# trig3_board_de0-nano_-_LTC6957.net
KiCad netlist of a schematic drawn in EAGLE
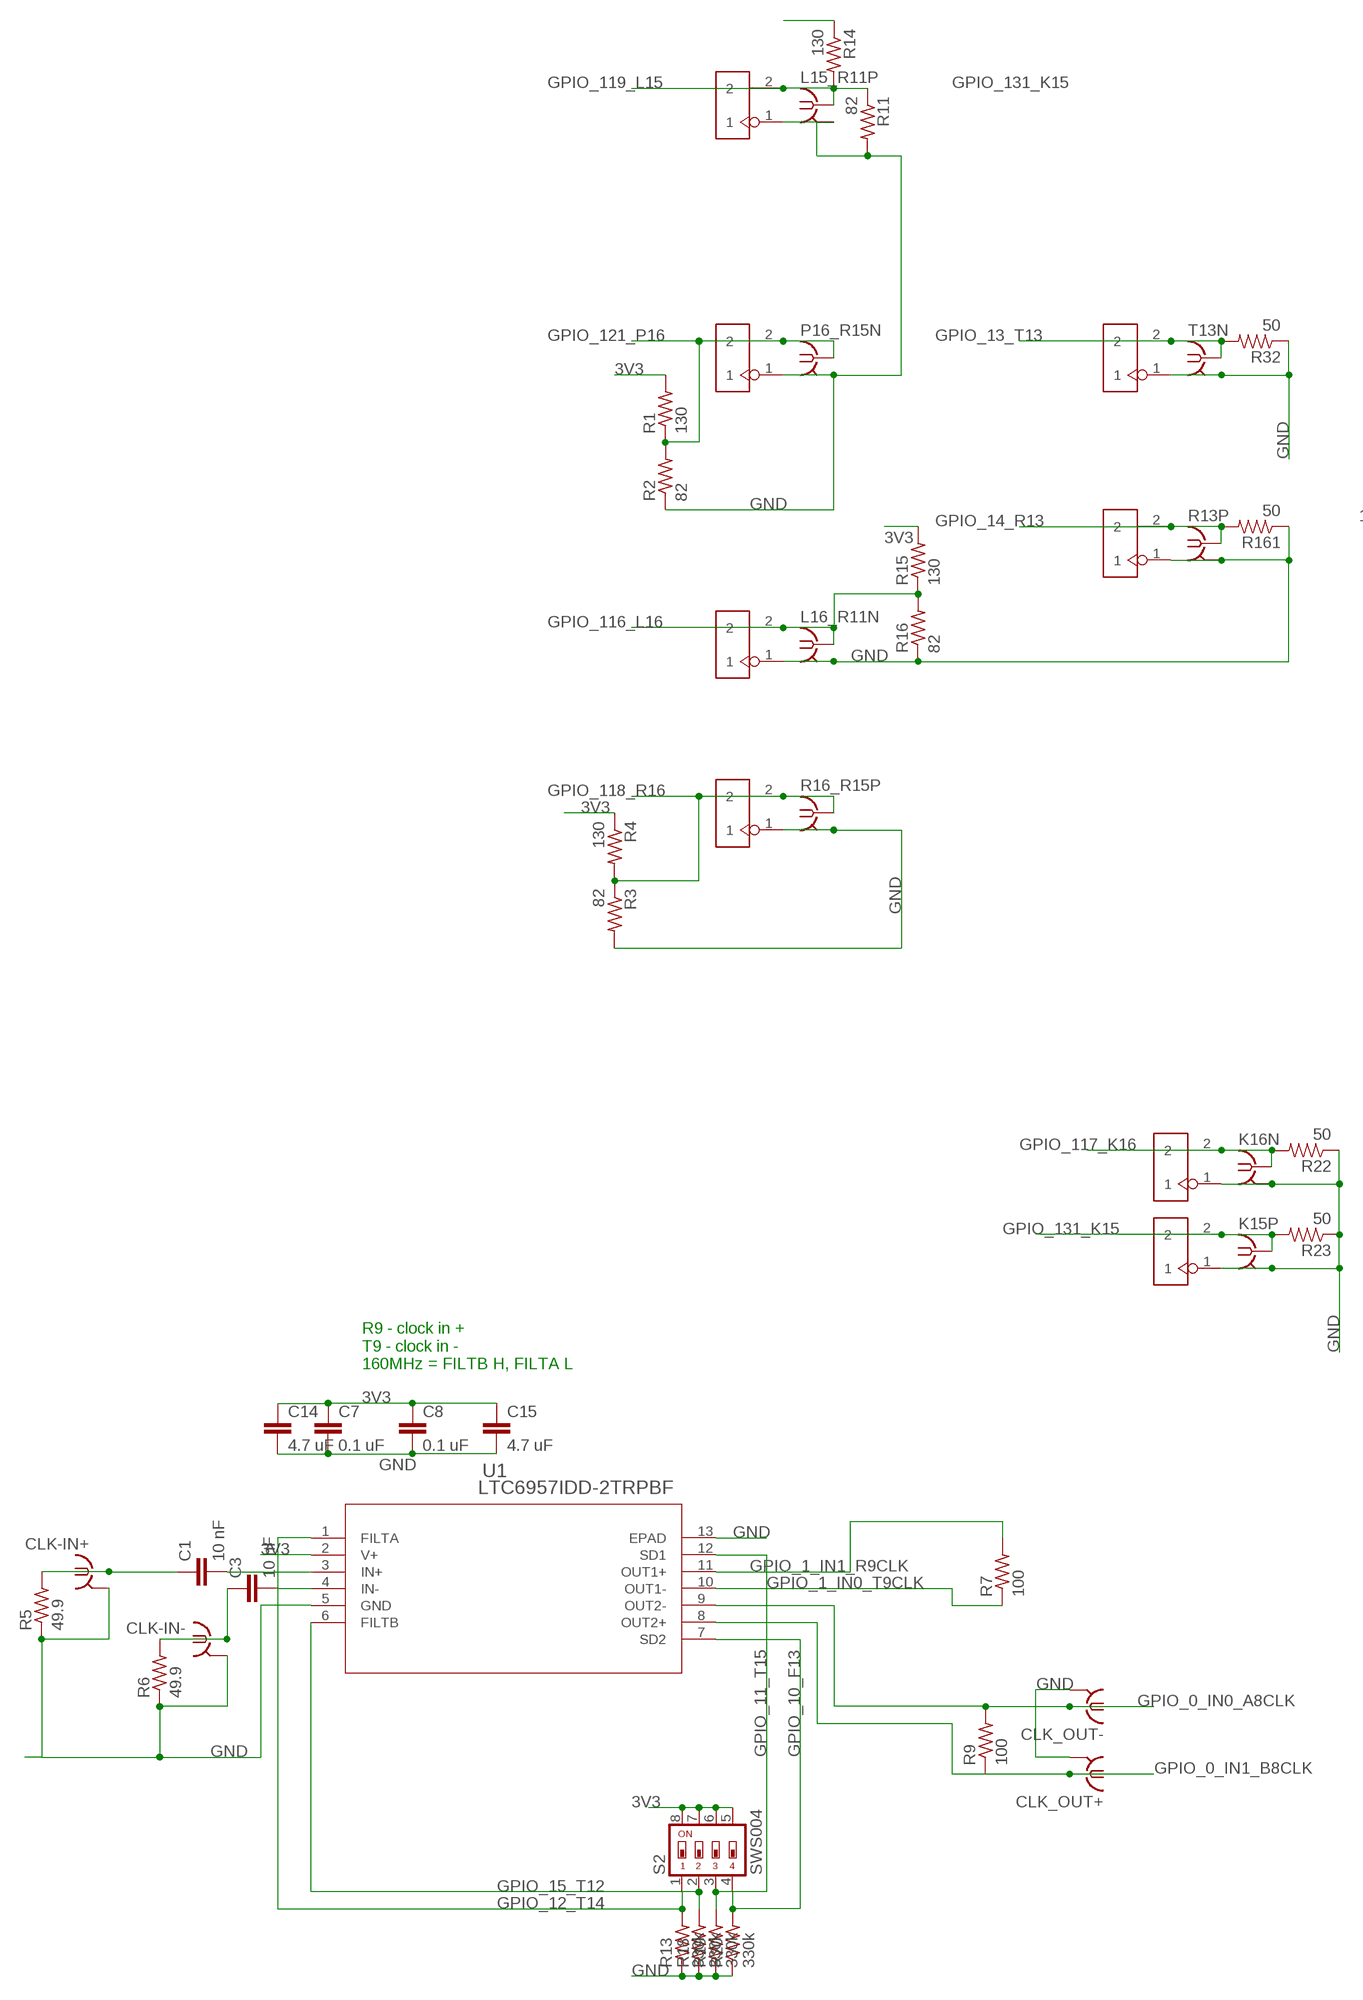
[diagram p0: schematic, sheet 1, part 1 of 2]
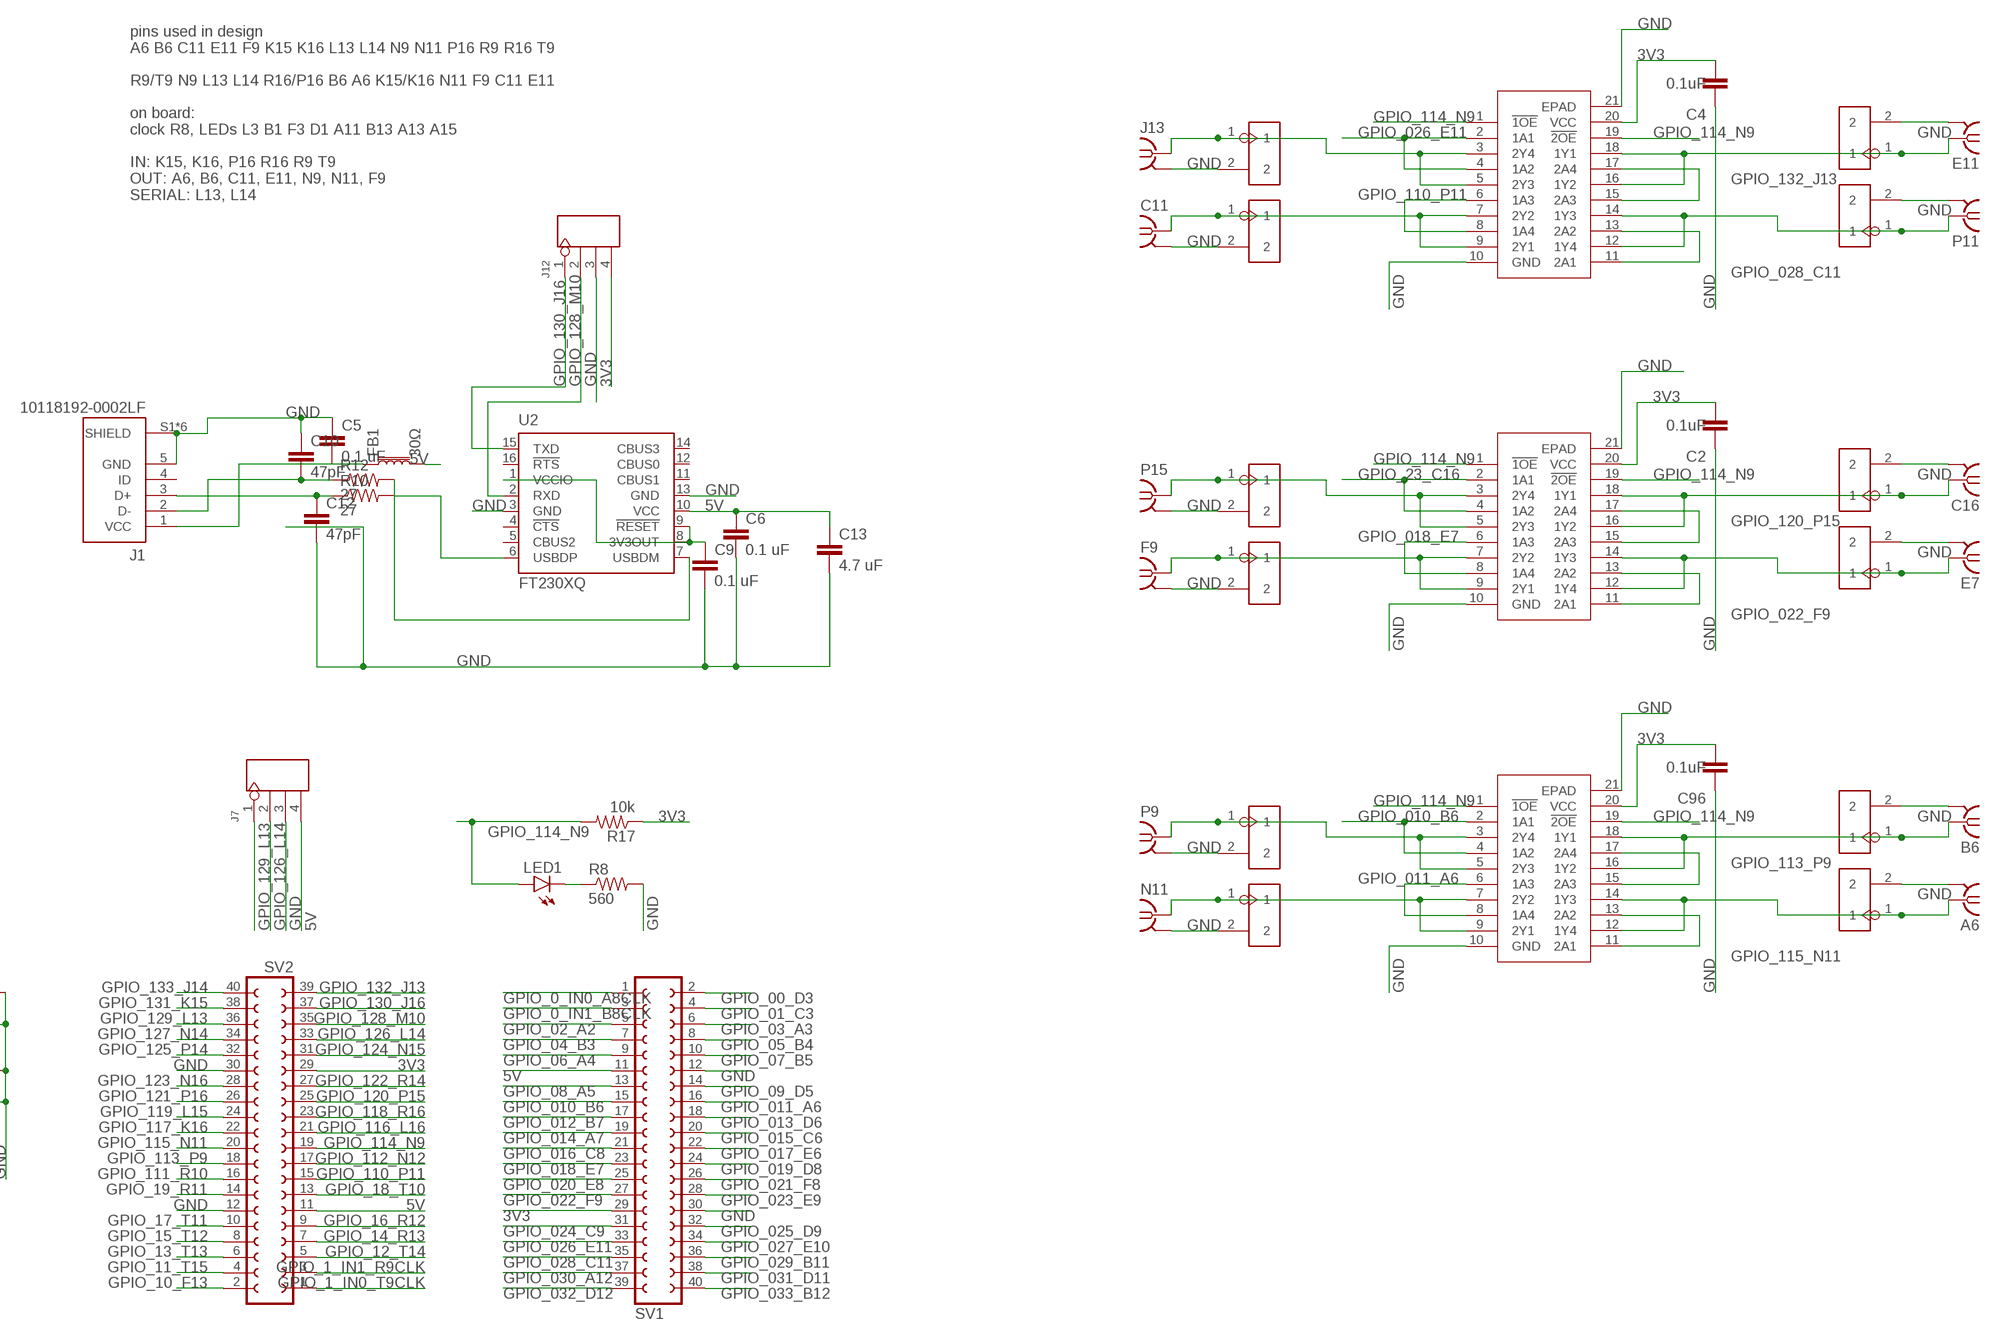
[diagram p1: schematic, sheet 1, part 2 of 2]

(export (version "E")
  (design (tool "Eeschema 10.0.6"))
  (components
    (comp (ref "A6")
      (value "BU-SMB-V")
      (footprint "eagle-import:BU-SMB-V")
      (fields (field (name "LCSC_PART#") "C496549"))
      (libsource (lib "eagle-import") (part "BU-SMB-V"))
    )
    (comp (ref "B6")
      (value "BU-SMB-V")
      (footprint "eagle-import:BU-SMB-V")
      (fields (field (name "LCSC_PART#") "C496549"))
      (libsource (lib "eagle-import") (part "BU-SMB-V"))
    )
    (comp (ref "C1")
      (value "10 nF")
      (footprint "eagle-import:C0603")
      (fields (field (name "LCSC_PART#") "C57112"))
      (libsource (lib "eagle-import") (part "C-EUC0603"))
    )
    (comp (ref "C2")
      (value "0.1uF")
      (footprint "eagle-import:C0603")
      (fields (field (name "LCSC_PART#") "C14663"))
      (libsource (lib "eagle-import") (part "C-EUC0603"))
    )
    (comp (ref "C3")
      (value "10 nF")
      (footprint "eagle-import:C0603")
      (fields (field (name "LCSC_PART#") "C57112"))
      (libsource (lib "eagle-import") (part "C-EUC0603"))
    )
    (comp (ref "C4")
      (value "0.1uF")
      (footprint "eagle-import:C0603")
      (fields (field (name "LCSC_PART#") "C14663"))
      (libsource (lib "eagle-import") (part "C-EUC0603"))
    )
    (comp (ref "C5")
      (value "0.1 uF")
      (footprint "eagle-import:C0603")
      (fields (field (name "LCSC_PART#") "C14663"))
      (libsource (lib "eagle-import") (part "C-EUC0603"))
    )
    (comp (ref "C6")
      (value "0.1 uF")
      (footprint "eagle-import:C0603")
      (fields (field (name "LCSC_PART#") "C14663"))
      (libsource (lib "eagle-import") (part "C-EUC0603"))
    )
    (comp (ref "C7")
      (value "0.1 uF")
      (footprint "eagle-import:C0603")
      (fields (field (name "LCSC_PART#") "C14663"))
      (libsource (lib "eagle-import") (part "C-EUC0603"))
    )
    (comp (ref "C8")
      (value "0.1 uF")
      (footprint "eagle-import:C0603")
      (fields (field (name "LCSC_PART#") "C14663"))
      (libsource (lib "eagle-import") (part "C-EUC0603"))
    )
    (comp (ref "C9")
      (value "0.1 uF")
      (footprint "eagle-import:C0603")
      (fields (field (name "LCSC_PART#") "C14663"))
      (libsource (lib "eagle-import") (part "C-EUC0603"))
    )
    (comp (ref "C10")
      (value "47pF")
      (footprint "eagle-import:C0603")
      (fields (field (name "LCSC_PART#") "C1671"))
      (libsource (lib "eagle-import") (part "C-EUC0603"))
    )
    (comp (ref "C11")
      (value "BU-SMB-V")
      (footprint "eagle-import:BU-SMB-V")
      (fields (field (name "LCSC_PART#") "C496549"))
      (libsource (lib "eagle-import") (part "BU-SMB-V"))
    )
    (comp (ref "C12")
      (value "47pF")
      (footprint "eagle-import:C0603")
      (fields (field (name "LCSC_PART#") "C1671"))
      (libsource (lib "eagle-import") (part "C-EUC0603"))
    )
    (comp (ref "C13")
      (value "4.7 uF")
      (footprint "eagle-import:C0603")
      (fields (field (name "LCSC_PART#") "C19666"))
      (libsource (lib "eagle-import") (part "C-EUC0603"))
    )
    (comp (ref "C14")
      (value "4.7 uF")
      (footprint "eagle-import:C0603")
      (fields (field (name "LCSC_PART#") "C19666"))
      (libsource (lib "eagle-import") (part "C-EUC0603"))
    )
    (comp (ref "C15")
      (value "4.7 uF")
      (footprint "eagle-import:C0603")
      (fields (field (name "LCSC_PART#") "C19666"))
      (libsource (lib "eagle-import") (part "C-EUC0603"))
    )
    (comp (ref "C16")
      (value "BU-SMB-V")
      (footprint "eagle-import:BU-SMB-V")
      (fields (field (name "LCSC_PART#") "C496549"))
      (libsource (lib "eagle-import") (part "BU-SMB-V"))
    )
    (comp (ref "C96")
      (value "0.1uF")
      (footprint "eagle-import:C0603")
      (fields (field (name "LCSC_PART#") "C14663"))
      (libsource (lib "eagle-import") (part "C-EUC0603"))
    )
    (comp (ref "CLK-IN+")
      (value "BU-SMB-V")
      (footprint "eagle-import:BU-SMB-V")
      (fields (field (name "LCSC_PART#") "C496549"))
      (libsource (lib "eagle-import") (part "BU-SMB-V"))
    )
    (comp (ref "CLK-IN-")
      (value "BU-SMB-V")
      (footprint "eagle-import:BU-SMB-V")
      (fields (field (name "LCSC_PART#") "C496549"))
      (libsource (lib "eagle-import") (part "BU-SMB-V"))
    )
    (comp (ref "CLK_OUT+")
      (value "BU-SMB-V")
      (footprint "eagle-import:BU-SMB-V")
      (fields (field (name "LCSC_PART#") "C496549"))
      (libsource (lib "eagle-import") (part "BU-SMB-V"))
    )
    (comp (ref "CLK_OUT-")
      (value "BU-SMB-V")
      (footprint "eagle-import:BU-SMB-V")
      (fields (field (name "LCSC_PART#") "C496549"))
      (libsource (lib "eagle-import") (part "BU-SMB-V"))
    )
    (comp (ref "E7")
      (value "BU-SMB-V")
      (footprint "eagle-import:BU-SMB-V")
      (fields (field (name "LCSC_PART#") "C496549"))
      (libsource (lib "eagle-import") (part "BU-SMB-V"))
    )
    (comp (ref "E11")
      (value "BU-SMB-V")
      (footprint "eagle-import:BU-SMB-V")
      (fields (field (name "LCSC_PART#") "C496549"))
      (libsource (lib "eagle-import") (part "BU-SMB-V"))
    )
    (comp (ref "F9")
      (value "BU-SMB-V")
      (footprint "eagle-import:BU-SMB-V")
      (fields (field (name "LCSC_PART#") "C496549"))
      (libsource (lib "eagle-import") (part "BU-SMB-V"))
    )
    (comp (ref "FB1")
      (value "30Ω")
      (footprint "eagle-import:0603")
      (fields (field (name "LCSC_PART#") "C1002"))
      (libsource (lib "eagle-import") (part "FERRITE_BEAD-0603-30OHM-100MHZ"))
    )
    (comp (ref "J1")
      (value "10118192-0002LF")
      (footprint "eagle-import:AMPHENOL_10118192-0002LF")
      (fields (field (name "MANUFACTURER") "Amphenol") (field (name "LCSC_PART#") "C132564"))
      (libsource (lib "eagle-import") (part "10118192-0002LF"))
    )
    (comp (ref "J7")
      (value "4p-2.54")
      (footprint "eagle-import:H4-2.54")
      (fields (field (name "MPN") "F185-1104A1BSYA1"))
      (libsource (lib "eagle-import") (part "DIP-BLACK-FEMALE-HEADER-VERT(4P-2.54)"))
    )
    (comp (ref "J12")
      (value "4p-2.54")
      (footprint "eagle-import:H4-2.54")
      (fields (field (name "MPN") "F185-1104A1BSYA1"))
      (libsource (lib "eagle-import") (part "DIP-BLACK-FEMALE-HEADER-VERT(4P-2.54)"))
    )
    (comp (ref "J13")
      (value "BU-SMB-V")
      (footprint "eagle-import:BU-SMB-V")
      (fields (field (name "LCSC_PART#") "C496549"))
      (libsource (lib "eagle-import") (part "BU-SMB-V"))
    )
    (comp (ref "J17")
      (value "2p-2.54")
      (footprint "eagle-import:H2-2.54")
      (fields (field (name "MPN") "P125-1102A0BS116A1"))
      (libsource (lib "eagle-import") (part "DIP-BLACK-MALE-HEADER-VERT(2P-2.54)"))
    )
    (comp (ref "J23")
      (value "2p-2.54")
      (footprint "eagle-import:H2-2.54")
      (fields (field (name "MPN") "P125-1102A0BS116A1"))
      (libsource (lib "eagle-import") (part "DIP-BLACK-MALE-HEADER-VERT(2P-2.54)"))
    )
    (comp (ref "J24")
      (value "2p-2.54")
      (footprint "eagle-import:H2-2.54")
      (fields (field (name "MPN") "P125-1102A0BS116A1"))
      (libsource (lib "eagle-import") (part "DIP-BLACK-MALE-HEADER-VERT(2P-2.54)"))
    )
    (comp (ref "J32")
      (value "2p-2.54")
      (footprint "eagle-import:H2-2.54")
      (fields (field (name "MPN") "P125-1102A0BS116A1"))
      (libsource (lib "eagle-import") (part "DIP-BLACK-MALE-HEADER-VERT(2P-2.54)"))
    )
    (comp (ref "J34")
      (value "2p-2.54")
      (footprint "eagle-import:H2-2.54")
      (fields (field (name "MPN") "P125-1102A0BS116A1"))
      (libsource (lib "eagle-import") (part "DIP-BLACK-MALE-HEADER-VERT(2P-2.54)"))
    )
    (comp (ref "J38")
      (value "2p-2.54")
      (footprint "eagle-import:H2-2.54")
      (fields (field (name "MPN") "P125-1102A0BS116A1"))
      (libsource (lib "eagle-import") (part "DIP-BLACK-MALE-HEADER-VERT(2P-2.54)"))
    )
    (comp (ref "J42")
      (value "2p-2.54")
      (footprint "eagle-import:H2-2.54")
      (fields (field (name "MPN") "P125-1102A0BS116A1"))
      (libsource (lib "eagle-import") (part "DIP-BLACK-MALE-HEADER-VERT(2P-2.54)"))
    )
    (comp (ref "J43")
      (value "2p-2.54")
      (footprint "eagle-import:H2-2.54")
      (fields (field (name "MPN") "P125-1102A0BS116A1"))
      (libsource (lib "eagle-import") (part "DIP-BLACK-MALE-HEADER-VERT(2P-2.54)"))
    )
    (comp (ref "K15P")
      (value "BU-SMB-V")
      (footprint "eagle-import:BU-SMB-V")
      (fields (field (name "LCSC_PART#") "C496549"))
      (libsource (lib "eagle-import") (part "BU-SMB-V"))
    )
    (comp (ref "K16N")
      (value "BU-SMB-V")
      (footprint "eagle-import:BU-SMB-V")
      (fields (field (name "LCSC_PART#") "C496549"))
      (libsource (lib "eagle-import") (part "BU-SMB-V"))
    )
    (comp (ref "L15_R11P")
      (value "BU-SMB-V")
      (footprint "eagle-import:BU-SMB-V")
      (fields (field (name "LCSC_PART#") "C496549"))
      (libsource (lib "eagle-import") (part "BU-SMB-V"))
    )
    (comp (ref "L16_R11N")
      (value "BU-SMB-V")
      (footprint "eagle-import:BU-SMB-V")
      (fields (field (name "LCSC_PART#") "C496549"))
      (libsource (lib "eagle-import") (part "BU-SMB-V"))
    )
    (comp (ref "LED1")
      (value "red")
      (footprint "eagle-import:SML0805")
      (fields (field (name "LCSC_PART#") "C84256"))
      (libsource (lib "eagle-import") (part "LEDSML0805"))
    )
    (comp (ref "N11")
      (value "BU-SMB-V")
      (footprint "eagle-import:BU-SMB-V")
      (fields (field (name "LCSC_PART#") "C496549"))
      (libsource (lib "eagle-import") (part "BU-SMB-V"))
    )
    (comp (ref "OJ41")
      (value "2p-2.54")
      (footprint "eagle-import:H2-2.54")
      (fields (field (name "MPN") "P125-1102A0BS116A1"))
      (libsource (lib "eagle-import") (part "DIP-BLACK-MALE-HEADER-VERT(2P-2.54)"))
    )
    (comp (ref "OJ42")
      (value "2p-2.54")
      (footprint "eagle-import:H2-2.54")
      (fields (field (name "MPN") "P125-1102A0BS116A1"))
      (libsource (lib "eagle-import") (part "DIP-BLACK-MALE-HEADER-VERT(2P-2.54)"))
    )
    (comp (ref "OJ43")
      (value "2p-2.54")
      (footprint "eagle-import:H2-2.54")
      (fields (field (name "MPN") "P125-1102A0BS116A1"))
      (libsource (lib "eagle-import") (part "DIP-BLACK-MALE-HEADER-VERT(2P-2.54)"))
    )
    (comp (ref "OJ44")
      (value "2p-2.54")
      (footprint "eagle-import:H2-2.54")
      (fields (field (name "MPN") "P125-1102A0BS116A1"))
      (libsource (lib "eagle-import") (part "DIP-BLACK-MALE-HEADER-VERT(2P-2.54)"))
    )
    (comp (ref "OJ57")
      (value "2p-2.54")
      (footprint "eagle-import:H2-2.54")
      (fields (field (name "MPN") "P125-1102A0BS116A1"))
      (libsource (lib "eagle-import") (part "DIP-BLACK-MALE-HEADER-VERT(2P-2.54)"))
    )
    (comp (ref "OJ58")
      (value "2p-2.54")
      (footprint "eagle-import:H2-2.54")
      (fields (field (name "MPN") "P125-1102A0BS116A1"))
      (libsource (lib "eagle-import") (part "DIP-BLACK-MALE-HEADER-VERT(2P-2.54)"))
    )
    (comp (ref "OJ59")
      (value "2p-2.54")
      (footprint "eagle-import:H2-2.54")
      (fields (field (name "MPN") "P125-1102A0BS116A1"))
      (libsource (lib "eagle-import") (part "DIP-BLACK-MALE-HEADER-VERT(2P-2.54)"))
    )
    (comp (ref "OJ60")
      (value "2p-2.54")
      (footprint "eagle-import:H2-2.54")
      (fields (field (name "MPN") "P125-1102A0BS116A1"))
      (libsource (lib "eagle-import") (part "DIP-BLACK-MALE-HEADER-VERT(2P-2.54)"))
    )
    (comp (ref "OJ73")
      (value "2p-2.54")
      (footprint "eagle-import:H2-2.54")
      (fields (field (name "MPN") "P125-1102A0BS116A1"))
      (libsource (lib "eagle-import") (part "DIP-BLACK-MALE-HEADER-VERT(2P-2.54)"))
    )
    (comp (ref "OJ74")
      (value "2p-2.54")
      (footprint "eagle-import:H2-2.54")
      (fields (field (name "MPN") "P125-1102A0BS116A1"))
      (libsource (lib "eagle-import") (part "DIP-BLACK-MALE-HEADER-VERT(2P-2.54)"))
    )
    (comp (ref "OJ75")
      (value "2p-2.54")
      (footprint "eagle-import:H2-2.54")
      (fields (field (name "MPN") "P125-1102A0BS116A1"))
      (libsource (lib "eagle-import") (part "DIP-BLACK-MALE-HEADER-VERT(2P-2.54)"))
    )
    (comp (ref "OJ76")
      (value "2p-2.54")
      (footprint "eagle-import:H2-2.54")
      (fields (field (name "MPN") "P125-1102A0BS116A1"))
      (libsource (lib "eagle-import") (part "DIP-BLACK-MALE-HEADER-VERT(2P-2.54)"))
    )
    (comp (ref "P9")
      (value "BU-SMB-V")
      (footprint "eagle-import:BU-SMB-V")
      (fields (field (name "LCSC_PART#") "C496549"))
      (libsource (lib "eagle-import") (part "BU-SMB-V"))
    )
    (comp (ref "P11")
      (value "BU-SMB-V")
      (footprint "eagle-import:BU-SMB-V")
      (fields (field (name "LCSC_PART#") "C496549"))
      (libsource (lib "eagle-import") (part "BU-SMB-V"))
    )
    (comp (ref "P15")
      (value "BU-SMB-V")
      (footprint "eagle-import:BU-SMB-V")
      (fields (field (name "LCSC_PART#") "C496549"))
      (libsource (lib "eagle-import") (part "BU-SMB-V"))
    )
    (comp (ref "P16_R15N")
      (value "BU-SMB-V")
      (footprint "eagle-import:BU-SMB-V")
      (fields (field (name "LCSC_PART#") "C496549"))
      (libsource (lib "eagle-import") (part "BU-SMB-V"))
    )
    (comp (ref "R1")
      (value "130")
      (footprint "eagle-import:R0603")
      (fields (field (name "LCSC_PART#") "C22796"))
      (libsource (lib "eagle-import") (part "R-US_R0603"))
    )
    (comp (ref "R2")
      (value "82")
      (footprint "eagle-import:R0603")
      (fields (field (name "LCSC_PART#") "C23255"))
      (libsource (lib "eagle-import") (part "R-US_R0603"))
    )
    (comp (ref "R3")
      (value "82")
      (footprint "eagle-import:R0603")
      (fields (field (name "LCSC_PART#") "C23255"))
      (libsource (lib "eagle-import") (part "R-US_R0603"))
    )
    (comp (ref "R4")
      (value "130")
      (footprint "eagle-import:R0603")
      (fields (field (name "LCSC_PART#") "C22796"))
      (libsource (lib "eagle-import") (part "R-US_R0603"))
    )
    (comp (ref "R5")
      (value "49.9")
      (footprint "eagle-import:R0603")
      (fields (field (name "LCSC_PART#") "C23185"))
      (libsource (lib "eagle-import") (part "R-US_R0603"))
    )
    (comp (ref "R6")
      (value "49.9")
      (footprint "eagle-import:R0603")
      (fields (field (name "LCSC_PART#") "C23185"))
      (libsource (lib "eagle-import") (part "R-US_R0603"))
    )
    (comp (ref "R7")
      (value "100")
      (footprint "eagle-import:R0603")
      (fields (field (name "LCSC_PART#") "C22775"))
      (libsource (lib "eagle-import") (part "R-US_R0603"))
    )
    (comp (ref "R8")
      (value "560")
      (footprint "eagle-import:R0805")
      (fields (field (name "LCSC_PART#") "C28636"))
      (libsource (lib "eagle-import") (part "resistor_348_R-US_R0805"))
    )
    (comp (ref "R9")
      (value "100")
      (footprint "eagle-import:R0603")
      (fields (field (name "LCSC_PART#") "C22775"))
      (libsource (lib "eagle-import") (part "R-US_R0603"))
    )
    (comp (ref "R10")
      (value "27")
      (footprint "eagle-import:R0603")
      (fields (field (name "LCSC_PART#") "C25190"))
      (libsource (lib "eagle-import") (part "R-US_R0603"))
    )
    (comp (ref "R11")
      (value "82")
      (footprint "eagle-import:R0603")
      (fields (field (name "LCSC_PART#") "C23255"))
      (libsource (lib "eagle-import") (part "R-US_R0603"))
    )
    (comp (ref "R12")
      (value "27")
      (footprint "eagle-import:R0603")
      (fields (field (name "LCSC_PART#") "C25190"))
      (libsource (lib "eagle-import") (part "R-US_R0603"))
    )
    (comp (ref "R13")
      (value "330k")
      (footprint "eagle-import:R0603")
      (fields (field (name "LCSC_PART#") "C23137"))
      (libsource (lib "eagle-import") (part "R-US_R0603"))
    )
    (comp (ref "R13P")
      (value "BU-SMB-V")
      (footprint "eagle-import:BU-SMB-V")
      (fields (field (name "LCSC_PART#") "C496549"))
      (libsource (lib "eagle-import") (part "BU-SMB-V"))
    )
    (comp (ref "R14")
      (value "130")
      (footprint "eagle-import:R0603")
      (fields (field (name "LCSC_PART#") "C22796"))
      (libsource (lib "eagle-import") (part "R-US_R0603"))
    )
    (comp (ref "R15")
      (value "130")
      (footprint "eagle-import:R0603")
      (fields (field (name "LCSC_PART#") "C22796"))
      (libsource (lib "eagle-import") (part "R-US_R0603"))
    )
    (comp (ref "R16")
      (value "82")
      (footprint "eagle-import:R0603")
      (fields (field (name "LCSC_PART#") "C23255"))
      (libsource (lib "eagle-import") (part "R-US_R0603"))
    )
    (comp (ref "R16_R15P")
      (value "BU-SMB-V")
      (footprint "eagle-import:BU-SMB-V")
      (fields (field (name "LCSC_PART#") "C496549"))
      (libsource (lib "eagle-import") (part "BU-SMB-V"))
    )
    (comp (ref "R17")
      (value "10k")
      (footprint "eagle-import:AXIAL-0.3")
      (libsource (lib "eagle-import") (part "RESISTORAXIAL-0.3"))
    )
    (comp (ref "R18")
      (value "330k")
      (footprint "eagle-import:R0603")
      (fields (field (name "LCSC_PART#") "C23137"))
      (libsource (lib "eagle-import") (part "R-US_R0603"))
    )
    (comp (ref "R19")
      (value "330k")
      (footprint "eagle-import:R0603")
      (fields (field (name "LCSC_PART#") "C23137"))
      (libsource (lib "eagle-import") (part "R-US_R0603"))
    )
    (comp (ref "R20")
      (value "330k")
      (footprint "eagle-import:R0603")
      (fields (field (name "LCSC_PART#") "C23137"))
      (libsource (lib "eagle-import") (part "R-US_R0603"))
    )
    (comp (ref "R22")
      (value "50")
      (footprint "eagle-import:AXIAL-0.3")
      (libsource (lib "eagle-import") (part "RESISTORAXIAL-0.3"))
    )
    (comp (ref "R23")
      (value "50")
      (footprint "eagle-import:AXIAL-0.3")
      (libsource (lib "eagle-import") (part "RESISTORAXIAL-0.3"))
    )
    (comp (ref "R32")
      (value "50")
      (footprint "eagle-import:AXIAL-0.3")
      (libsource (lib "eagle-import") (part "RESISTORAXIAL-0.3"))
    )
    (comp (ref "R161")
      (value "50")
      (footprint "eagle-import:AXIAL-0.3")
      (libsource (lib "eagle-import") (part "RESISTORAXIAL-0.3"))
    )
    (comp (ref "S2")
      (value "SWS004")
      (footprint "eagle-import:SMS-004")
      (fields (field (name "LCSC_PART#") "C221954"))
      (libsource (lib "eagle-import") (part "SWS004"))
    )
    (comp (ref "SV1")
      (value "FE20-2")
      (footprint "eagle-import:FE20-2")
      (libsource (lib "eagle-import") (part "FE20-2"))
    )
    (comp (ref "SV2")
      (value "FE20-2")
      (footprint "eagle-import:FE20-2")
      (libsource (lib "eagle-import") (part "FE20-2"))
    )
    (comp (ref "T13N")
      (value "BU-SMB-V")
      (footprint "eagle-import:BU-SMB-V")
      (fields (field (name "LCSC_PART#") "C496549"))
      (libsource (lib "eagle-import") (part "BU-SMB-V"))
    )
    (comp (ref "U1")
      (value "LTC6957IDD-2TRPBF")
      (footprint "eagle-import:DFN-12_DD_LIT")
      (fields
        (field (name "MANUFACTURER_PART_NUMBER") "LTC6957IDD-2#TRPBF")
        (field (name "LCSC_PART#") "C689878")
        (field (name "COPYRIGHT") "Copyright (C) 2023 Ultra Librarian. All rights reserved.")
      )
      (libsource (lib "eagle-import") (part "LTC6957IDD-2TRPBF"))
    )
    (comp (ref "U2")
      (value "FT230XQ")
      (footprint "eagle-import:QFN16")
      (fields (field (name "LCSC_PART#") "C128629"))
      (libsource (lib "eagle-import") (part "FT230XQ"))
    )
    (comp (ref "U3")
      (value "SN74LVTH244ARGYR")
      (footprint "eagle-import:RGY20_3P05X2P05")
      (fields
        (field (name "LCSC_PART#") "C2869480")
        (field (name "COPYRIGHT") "Copyright (C) 2023 Ultra Librarian. All rights reserved.")
      )
      (libsource (lib "eagle-import") (part "SN74LVTH244ARGYR"))
    )
    (comp (ref "U4")
      (value "SN74LVTH244ARGYR")
      (footprint "eagle-import:RGY20_3P05X2P05")
      (fields
        (field (name "LCSC_PART#") "C2869480")
        (field (name "COPYRIGHT") "Copyright (C) 2023 Ultra Librarian. All rights reserved.")
      )
      (libsource (lib "eagle-import") (part "SN74LVTH244ARGYR"))
    )
    (comp (ref "U5")
      (value "SN74LVTH244ARGYR")
      (footprint "eagle-import:RGY20_3P05X2P05")
      (fields
        (field (name "LCSC_PART#") "C2869480")
        (field (name "COPYRIGHT") "Copyright (C) 2023 Ultra Librarian. All rights reserved.")
      )
      (libsource (lib "eagle-import") (part "SN74LVTH244ARGYR"))
    )
  )
  (nets
    (net (code "1") (name "/3V3") (class "Default")
      (node (ref "C14") (pin "1") (pinfunction "1_1") (pintype "passive"))
      (node (ref "C15") (pin "1") (pinfunction "1_1") (pintype "passive"))
      (node (ref "C2") (pin "2") (pinfunction "2_2") (pintype "passive"))
      (node (ref "C4") (pin "2") (pinfunction "2_2") (pintype "passive"))
      (node (ref "C7") (pin "1") (pinfunction "1_1") (pintype "passive"))
      (node (ref "C8") (pin "1") (pinfunction "1_1") (pintype "passive"))
      (node (ref "C96") (pin "2") (pinfunction "2_2") (pintype "passive"))
      (node (ref "J12") (pin "4") (pinfunction "P$4_4") (pintype "bidirectional"))
      (node (ref "R1") (pin "2") (pinfunction "2_2") (pintype "passive"))
      (node (ref "R14") (pin "1") (pinfunction "1_1") (pintype "passive"))
      (node (ref "R15") (pin "2") (pinfunction "2_2") (pintype "passive"))
      (node (ref "R17") (pin "P$1") (pinfunction "1_P$1") (pintype "passive"))
      (node (ref "R4") (pin "1") (pinfunction "1_1") (pintype "passive"))
      (node (ref "S2") (pin "5") (pinfunction "5_5") (pintype "passive"))
      (node (ref "S2") (pin "6") (pinfunction "6_6") (pintype "passive"))
      (node (ref "S2") (pin "7") (pinfunction "7_7") (pintype "passive"))
      (node (ref "S2") (pin "8") (pinfunction "8_8") (pintype "passive"))
      (node (ref "SV1") (pin "29") (pinfunction "29_29") (pintype "passive"))
      (node (ref "SV2") (pin "29") (pinfunction "29_29") (pintype "passive"))
      (node (ref "U1") (pin "2") (pinfunction "V+_2") (pintype "power_in"))
      (node (ref "U3") (pin "20") (pinfunction "VCC_20") (pintype "power_in"))
      (node (ref "U4") (pin "20") (pinfunction "VCC_20") (pintype "power_in"))
      (node (ref "U5") (pin "20") (pinfunction "VCC_20") (pintype "power_in"))
    )
    (net (code "2") (name "/5V") (class "Default")
      (node (ref "C13") (pin "1") (pinfunction "1_1") (pintype "passive"))
      (node (ref "C6") (pin "1") (pinfunction "1_1") (pintype "passive"))
      (node (ref "FB1") (pin "2") (pinfunction "2_2") (pintype "passive"))
      (node (ref "J7") (pin "4") (pinfunction "P$4_4") (pintype "bidirectional"))
      (node (ref "SV1") (pin "11") (pinfunction "11_11") (pintype "passive"))
      (node (ref "SV2") (pin "11") (pinfunction "11_11") (pintype "passive"))
      (node (ref "U2") (pin "10") (pinfunction "VCC_10") (pintype "power_in"))
    )
    (net (code "3") (name "/GND") (class "Default")
      (node (ref "A6") (pin "2") (pinfunction "2_2") (pintype "passive"))
      (node (ref "A6") (pin "3") (pinfunction "2_3") (pintype "passive"))
      (node (ref "A6") (pin "4") (pinfunction "2_4") (pintype "passive"))
      (node (ref "A6") (pin "5") (pinfunction "2_5") (pintype "passive"))
      (node (ref "B6") (pin "2") (pinfunction "2_2") (pintype "passive"))
      (node (ref "B6") (pin "3") (pinfunction "2_3") (pintype "passive"))
      (node (ref "B6") (pin "4") (pinfunction "2_4") (pintype "passive"))
      (node (ref "B6") (pin "5") (pinfunction "2_5") (pintype "passive"))
      (node (ref "C10") (pin "1") (pinfunction "1_1") (pintype "passive"))
      (node (ref "C11") (pin "2") (pinfunction "2_2") (pintype "passive"))
      (node (ref "C11") (pin "3") (pinfunction "2_3") (pintype "passive"))
      (node (ref "C11") (pin "4") (pinfunction "2_4") (pintype "passive"))
      (node (ref "C11") (pin "5") (pinfunction "2_5") (pintype "passive"))
      (node (ref "C12") (pin "2") (pinfunction "2_2") (pintype "passive"))
      (node (ref "C13") (pin "2") (pinfunction "2_2") (pintype "passive"))
      (node (ref "C14") (pin "2") (pinfunction "2_2") (pintype "passive"))
      (node (ref "C15") (pin "2") (pinfunction "2_2") (pintype "passive"))
      (node (ref "C16") (pin "2") (pinfunction "2_2") (pintype "passive"))
      (node (ref "C16") (pin "3") (pinfunction "2_3") (pintype "passive"))
      (node (ref "C16") (pin "4") (pinfunction "2_4") (pintype "passive"))
      (node (ref "C16") (pin "5") (pinfunction "2_5") (pintype "passive"))
      (node (ref "C2") (pin "1") (pinfunction "1_1") (pintype "passive"))
      (node (ref "C4") (pin "1") (pinfunction "1_1") (pintype "passive"))
      (node (ref "C5") (pin "1") (pinfunction "1_1") (pintype "passive"))
      (node (ref "C6") (pin "2") (pinfunction "2_2") (pintype "passive"))
      (node (ref "C7") (pin "2") (pinfunction "2_2") (pintype "passive"))
      (node (ref "C8") (pin "2") (pinfunction "2_2") (pintype "passive"))
      (node (ref "C9") (pin "2") (pinfunction "2_2") (pintype "passive"))
      (node (ref "C96") (pin "1") (pinfunction "1_1") (pintype "passive"))
      (node (ref "CLK-IN+") (pin "2") (pinfunction "2_2") (pintype "passive"))
      (node (ref "CLK-IN+") (pin "3") (pinfunction "2_3") (pintype "passive"))
      (node (ref "CLK-IN+") (pin "4") (pinfunction "2_4") (pintype "passive"))
      (node (ref "CLK-IN+") (pin "5") (pinfunction "2_5") (pintype "passive"))
      (node (ref "CLK-IN-") (pin "2") (pinfunction "2_2") (pintype "passive"))
      (node (ref "CLK-IN-") (pin "3") (pinfunction "2_3") (pintype "passive"))
      (node (ref "CLK-IN-") (pin "4") (pinfunction "2_4") (pintype "passive"))
      (node (ref "CLK-IN-") (pin "5") (pinfunction "2_5") (pintype "passive"))
      (node (ref "CLK_OUT+") (pin "2") (pinfunction "2_2") (pintype "passive"))
      (node (ref "CLK_OUT+") (pin "3") (pinfunction "2_3") (pintype "passive"))
      (node (ref "CLK_OUT+") (pin "4") (pinfunction "2_4") (pintype "passive"))
      (node (ref "CLK_OUT+") (pin "5") (pinfunction "2_5") (pintype "passive"))
      (node (ref "CLK_OUT-") (pin "2") (pinfunction "2_2") (pintype "passive"))
      (node (ref "CLK_OUT-") (pin "3") (pinfunction "2_3") (pintype "passive"))
      (node (ref "CLK_OUT-") (pin "4") (pinfunction "2_4") (pintype "passive"))
      (node (ref "CLK_OUT-") (pin "5") (pinfunction "2_5") (pintype "passive"))
      (node (ref "E11") (pin "2") (pinfunction "2_2") (pintype "passive"))
      (node (ref "E11") (pin "3") (pinfunction "2_3") (pintype "passive"))
      (node (ref "E11") (pin "4") (pinfunction "2_4") (pintype "passive"))
      (node (ref "E11") (pin "5") (pinfunction "2_5") (pintype "passive"))
      (node (ref "E7") (pin "2") (pinfunction "2_2") (pintype "passive"))
      (node (ref "E7") (pin "3") (pinfunction "2_3") (pintype "passive"))
      (node (ref "E7") (pin "4") (pinfunction "2_4") (pintype "passive"))
      (node (ref "E7") (pin "5") (pinfunction "2_5") (pintype "passive"))
      (node (ref "F9") (pin "2") (pinfunction "2_2") (pintype "passive"))
      (node (ref "F9") (pin "3") (pinfunction "2_3") (pintype "passive"))
      (node (ref "F9") (pin "4") (pinfunction "2_4") (pintype "passive"))
      (node (ref "F9") (pin "5") (pinfunction "2_5") (pintype "passive"))
      (node (ref "J1") (pin "5") (pinfunction "GND_5") (pintype "power_in"))
      (node (ref "J1") (pin "S1") (pinfunction "SHIELD_S1") (pintype "passive"))
      (node (ref "J1") (pin "S2") (pinfunction "SHIELD_S2") (pintype "passive"))
      (node (ref "J1") (pin "S3") (pinfunction "SHIELD_S3") (pintype "passive"))
      (node (ref "J1") (pin "S4") (pinfunction "SHIELD_S4") (pintype "passive"))
      (node (ref "J1") (pin "S5") (pinfunction "SHIELD_S5") (pintype "passive"))
      (node (ref "J1") (pin "S6") (pinfunction "SHIELD_S6") (pintype "passive"))
      (node (ref "J12") (pin "3") (pinfunction "P$3_3") (pintype "bidirectional"))
      (node (ref "J13") (pin "2") (pinfunction "2_2") (pintype "passive"))
      (node (ref "J13") (pin "3") (pinfunction "2_3") (pintype "passive"))
      (node (ref "J13") (pin "4") (pinfunction "2_4") (pintype "passive"))
      (node (ref "J13") (pin "5") (pinfunction "2_5") (pintype "passive"))
      (node (ref "J17") (pin "1") (pinfunction "1_1") (pintype "bidirectional"))
      (node (ref "J23") (pin "1") (pinfunction "1_1") (pintype "bidirectional"))
      (node (ref "J24") (pin "1") (pinfunction "1_1") (pintype "bidirectional"))
      (node (ref "J32") (pin "1") (pinfunction "1_1") (pintype "bidirectional"))
      (node (ref "J34") (pin "1") (pinfunction "1_1") (pintype "bidirectional"))
      (node (ref "J38") (pin "1") (pinfunction "1_1") (pintype "bidirectional"))
      (node (ref "J42") (pin "1") (pinfunction "1_1") (pintype "bidirectional"))
      (node (ref "J43") (pin "1") (pinfunction "1_1") (pintype "bidirectional"))
      (node (ref "J7") (pin "3") (pinfunction "P$3_3") (pintype "bidirectional"))
      (node (ref "K15P") (pin "2") (pinfunction "2_2") (pintype "passive"))
      (node (ref "K15P") (pin "3") (pinfunction "2_3") (pintype "passive"))
      (node (ref "K15P") (pin "4") (pinfunction "2_4") (pintype "passive"))
      (node (ref "K15P") (pin "5") (pinfunction "2_5") (pintype "passive"))
      (node (ref "K16N") (pin "2") (pinfunction "2_2") (pintype "passive"))
      (node (ref "K16N") (pin "3") (pinfunction "2_3") (pintype "passive"))
      (node (ref "K16N") (pin "4") (pinfunction "2_4") (pintype "passive"))
      (node (ref "K16N") (pin "5") (pinfunction "2_5") (pintype "passive"))
      (node (ref "L15_R11P") (pin "2") (pinfunction "2_2") (pintype "passive"))
      (node (ref "L15_R11P") (pin "3") (pinfunction "2_3") (pintype "passive"))
      (node (ref "L15_R11P") (pin "4") (pinfunction "2_4") (pintype "passive"))
      (node (ref "L15_R11P") (pin "5") (pinfunction "2_5") (pintype "passive"))
      (node (ref "L16_R11N") (pin "2") (pinfunction "2_2") (pintype "passive"))
      (node (ref "L16_R11N") (pin "3") (pinfunction "2_3") (pintype "passive"))
      (node (ref "L16_R11N") (pin "4") (pinfunction "2_4") (pintype "passive"))
      (node (ref "L16_R11N") (pin "5") (pinfunction "2_5") (pintype "passive"))
      (node (ref "N11") (pin "2") (pinfunction "2_2") (pintype "passive"))
      (node (ref "N11") (pin "3") (pinfunction "2_3") (pintype "passive"))
      (node (ref "N11") (pin "4") (pinfunction "2_4") (pintype "passive"))
      (node (ref "N11") (pin "5") (pinfunction "2_5") (pintype "passive"))
      (node (ref "OJ41") (pin "2") (pinfunction "2_2") (pintype "bidirectional"))
      (node (ref "OJ42") (pin "2") (pinfunction "2_2") (pintype "bidirectional"))
      (node (ref "OJ43") (pin "2") (pinfunction "2_2") (pintype "bidirectional"))
      (node (ref "OJ44") (pin "2") (pinfunction "2_2") (pintype "bidirectional"))
      (node (ref "OJ57") (pin "2") (pinfunction "2_2") (pintype "bidirectional"))
      (node (ref "OJ58") (pin "2") (pinfunction "2_2") (pintype "bidirectional"))
      (node (ref "OJ59") (pin "2") (pinfunction "2_2") (pintype "bidirectional"))
      (node (ref "OJ60") (pin "2") (pinfunction "2_2") (pintype "bidirectional"))
      (node (ref "OJ73") (pin "2") (pinfunction "2_2") (pintype "bidirectional"))
      (node (ref "OJ74") (pin "2") (pinfunction "2_2") (pintype "bidirectional"))
      (node (ref "OJ75") (pin "2") (pinfunction "2_2") (pintype "bidirectional"))
      (node (ref "OJ76") (pin "2") (pinfunction "2_2") (pintype "bidirectional"))
      (node (ref "P11") (pin "2") (pinfunction "2_2") (pintype "passive"))
      (node (ref "P11") (pin "3") (pinfunction "2_3") (pintype "passive"))
      (node (ref "P11") (pin "4") (pinfunction "2_4") (pintype "passive"))
      (node (ref "P11") (pin "5") (pinfunction "2_5") (pintype "passive"))
      (node (ref "P15") (pin "2") (pinfunction "2_2") (pintype "passive"))
      (node (ref "P15") (pin "3") (pinfunction "2_3") (pintype "passive"))
      (node (ref "P15") (pin "4") (pinfunction "2_4") (pintype "passive"))
      (node (ref "P15") (pin "5") (pinfunction "2_5") (pintype "passive"))
      (node (ref "P16_R15N") (pin "2") (pinfunction "2_2") (pintype "passive"))
      (node (ref "P16_R15N") (pin "3") (pinfunction "2_3") (pintype "passive"))
      (node (ref "P16_R15N") (pin "4") (pinfunction "2_4") (pintype "passive"))
      (node (ref "P16_R15N") (pin "5") (pinfunction "2_5") (pintype "passive"))
      (node (ref "P9") (pin "2") (pinfunction "2_2") (pintype "passive"))
      (node (ref "P9") (pin "3") (pinfunction "2_3") (pintype "passive"))
      (node (ref "P9") (pin "4") (pinfunction "2_4") (pintype "passive"))
      (node (ref "P9") (pin "5") (pinfunction "2_5") (pintype "passive"))
      (node (ref "R11") (pin "2") (pinfunction "2_2") (pintype "passive"))
      (node (ref "R13") (pin "1") (pinfunction "1_1") (pintype "passive"))
      (node (ref "R13P") (pin "2") (pinfunction "2_2") (pintype "passive"))
      (node (ref "R13P") (pin "3") (pinfunction "2_3") (pintype "passive"))
      (node (ref "R13P") (pin "4") (pinfunction "2_4") (pintype "passive"))
      (node (ref "R13P") (pin "5") (pinfunction "2_5") (pintype "passive"))
      (node (ref "R16") (pin "1") (pinfunction "1_1") (pintype "passive"))
      (node (ref "R161") (pin "P$1") (pinfunction "1_P$1") (pintype "passive"))
      (node (ref "R16_R15P") (pin "2") (pinfunction "2_2") (pintype "passive"))
      (node (ref "R16_R15P") (pin "3") (pinfunction "2_3") (pintype "passive"))
      (node (ref "R16_R15P") (pin "4") (pinfunction "2_4") (pintype "passive"))
      (node (ref "R16_R15P") (pin "5") (pinfunction "2_5") (pintype "passive"))
      (node (ref "R18") (pin "1") (pinfunction "1_1") (pintype "passive"))
      (node (ref "R19") (pin "1") (pinfunction "1_1") (pintype "passive"))
      (node (ref "R2") (pin "1") (pinfunction "1_1") (pintype "passive"))
      (node (ref "R20") (pin "1") (pinfunction "1_1") (pintype "passive"))
      (node (ref "R22") (pin "P$1") (pinfunction "1_P$1") (pintype "passive"))
      (node (ref "R23") (pin "P$1") (pinfunction "1_P$1") (pintype "passive"))
      (node (ref "R3") (pin "2") (pinfunction "2_2") (pintype "passive"))
      (node (ref "R32") (pin "P$1") (pinfunction "1_P$1") (pintype "passive"))
      (node (ref "R5") (pin "1") (pinfunction "1_1") (pintype "passive"))
      (node (ref "R6") (pin "1") (pinfunction "1_1") (pintype "passive"))
      (node (ref "R8") (pin "2") (pinfunction "2_2") (pintype "passive"))
      (node (ref "SV1") (pin "12") (pinfunction "12_12") (pintype "passive"))
      (node (ref "SV1") (pin "30") (pinfunction "30_30") (pintype "passive"))
      (node (ref "SV2") (pin "12") (pinfunction "12_12") (pintype "passive"))
      (node (ref "SV2") (pin "30") (pinfunction "30_30") (pintype "passive"))
      (node (ref "T13N") (pin "2") (pinfunction "2_2") (pintype "passive"))
      (node (ref "T13N") (pin "3") (pinfunction "2_3") (pintype "passive"))
      (node (ref "T13N") (pin "4") (pinfunction "2_4") (pintype "passive"))
      (node (ref "T13N") (pin "5") (pinfunction "2_5") (pintype "passive"))
      (node (ref "U1") (pin "13") (pinfunction "EPAD_13") (pintype "passive"))
      (node (ref "U1") (pin "5") (pinfunction "GND_5") (pintype "power_in"))
      (node (ref "U2") (pin "13") (pinfunction "GND_13") (pintype "power_in"))
      (node (ref "U2") (pin "3") (pinfunction "GND_3") (pintype "power_in"))
      (node (ref "U3") (pin "10") (pinfunction "GND_10") (pintype "power_in"))
      (node (ref "U3") (pin "21") (pinfunction "EPAD_21") (pintype "passive"))
      (node (ref "U4") (pin "10") (pinfunction "GND_10") (pintype "power_in"))
      (node (ref "U4") (pin "21") (pinfunction "EPAD_21") (pintype "passive"))
      (node (ref "U5") (pin "10") (pinfunction "GND_10") (pintype "power_in"))
      (node (ref "U5") (pin "21") (pinfunction "EPAD_21") (pintype "passive"))
    )
    (net (code "4") (name "/GPIO_00_D3") (class "Default")
      (node (ref "SV1") (pin "2") (pinfunction "2_2") (pintype "passive"))
    )
    (net (code "5") (name "/GPIO_0_IN0_A8CLK") (class "Default")
      (node (ref "CLK_OUT-") (pin "1") (pinfunction "1_1") (pintype "passive"))
      (node (ref "R9") (pin "2") (pinfunction "2_2") (pintype "passive"))
      (node (ref "SV1") (pin "1") (pinfunction "1_1") (pintype "passive"))
      (node (ref "U1") (pin "9") (pinfunction "OUT2-_9") (pintype "output"))
    )
    (net (code "6") (name "/GPIO_0_IN1_B8CLK") (class "Default")
      (node (ref "CLK_OUT+") (pin "1") (pinfunction "1_1") (pintype "passive"))
      (node (ref "R9") (pin "1") (pinfunction "1_1") (pintype "passive"))
      (node (ref "SV1") (pin "3") (pinfunction "3_3") (pintype "passive"))
      (node (ref "U1") (pin "8") (pinfunction "OUT2+_8") (pintype "output"))
    )
    (net (code "7") (name "/GPIO_01_C3") (class "Default")
      (node (ref "SV1") (pin "4") (pinfunction "4_4") (pintype "passive"))
    )
    (net (code "8") (name "/GPIO_1_IN0_T9CLK") (class "Default")
      (node (ref "R7") (pin "1") (pinfunction "1_1") (pintype "passive"))
      (node (ref "SV2") (pin "1") (pinfunction "1_1") (pintype "passive"))
      (node (ref "U1") (pin "10") (pinfunction "OUT1-_10") (pintype "output"))
    )
    (net (code "9") (name "/GPIO_1_IN1_R9CLK") (class "Default")
      (node (ref "R7") (pin "2") (pinfunction "2_2") (pintype "passive"))
      (node (ref "SV2") (pin "3") (pinfunction "3_3") (pintype "passive"))
      (node (ref "U1") (pin "11") (pinfunction "OUT1+_11") (pintype "power_in"))
    )
    (net (code "10") (name "/GPIO_02_A2") (class "Default")
      (node (ref "SV1") (pin "5") (pinfunction "5_5") (pintype "passive"))
    )
    (net (code "11") (name "/GPIO_03_A3") (class "Default")
      (node (ref "SV1") (pin "6") (pinfunction "6_6") (pintype "passive"))
    )
    (net (code "12") (name "/GPIO_04_B3") (class "Default")
      (node (ref "SV1") (pin "7") (pinfunction "7_7") (pintype "passive"))
    )
    (net (code "13") (name "/GPIO_05_B4") (class "Default")
      (node (ref "SV1") (pin "8") (pinfunction "8_8") (pintype "passive"))
    )
    (net (code "14") (name "/GPIO_06_A4") (class "Default")
      (node (ref "SV1") (pin "9") (pinfunction "9_9") (pintype "passive"))
    )
    (net (code "15") (name "/GPIO_07_B5") (class "Default")
      (node (ref "SV1") (pin "10") (pinfunction "10_10") (pintype "passive"))
    )
    (net (code "16") (name "/GPIO_08_A5") (class "Default")
      (node (ref "SV1") (pin "13") (pinfunction "13_13") (pintype "passive"))
    )
    (net (code "17") (name "/GPIO_09_D5") (class "Default")
      (node (ref "SV1") (pin "14") (pinfunction "14_14") (pintype "passive"))
    )
    (net (code "18") (name "/GPIO_010_B6") (class "Default")
      (node (ref "SV1") (pin "15") (pinfunction "15_15") (pintype "passive"))
      (node (ref "U5") (pin "2") (pinfunction "1A1_2") (pintype "input"))
      (node (ref "U5") (pin "4") (pinfunction "1A2_4") (pintype "input"))
    )
    (net (code "19") (name "/GPIO_10_F13") (class "Default")
      (node (ref "R20") (pin "2") (pinfunction "2_2") (pintype "passive"))
      (node (ref "S2") (pin "4") (pinfunction "4_4") (pintype "passive"))
      (node (ref "SV2") (pin "2") (pinfunction "2_2") (pintype "passive"))
      (node (ref "U1") (pin "7") (pinfunction "SD2_7") (pintype "output"))
    )
    (net (code "20") (name "/GPIO_011_A6") (class "Default")
      (node (ref "SV1") (pin "16") (pinfunction "16_16") (pintype "passive"))
      (node (ref "U5") (pin "6") (pinfunction "1A3_6") (pintype "input"))
      (node (ref "U5") (pin "8") (pinfunction "1A4_8") (pintype "input"))
    )
    (net (code "21") (name "/GPIO_11_T15") (class "Default")
      (node (ref "R19") (pin "2") (pinfunction "2_2") (pintype "passive"))
      (node (ref "S2") (pin "3") (pinfunction "3_3") (pintype "passive"))
      (node (ref "SV2") (pin "4") (pinfunction "4_4") (pintype "passive"))
      (node (ref "U1") (pin "12") (pinfunction "SD1_12") (pintype "output"))
    )
    (net (code "22") (name "/GPIO_012_B7") (class "Default")
      (node (ref "SV1") (pin "17") (pinfunction "17_17") (pintype "passive"))
    )
    (net (code "23") (name "/GPIO_12_T14") (class "Default")
      (node (ref "R13") (pin "2") (pinfunction "2_2") (pintype "passive"))
      (node (ref "S2") (pin "1") (pinfunction "1_1") (pintype "passive"))
      (node (ref "SV2") (pin "5") (pinfunction "5_5") (pintype "passive"))
      (node (ref "U1") (pin "1") (pinfunction "FILTA_1") (pintype "input"))
    )
    (net (code "24") (name "/GPIO_013_D6") (class "Default")
      (node (ref "SV1") (pin "18") (pinfunction "18_18") (pintype "passive"))
    )
    (net (code "25") (name "/GPIO_13_T13") (class "Default")
      (node (ref "J38") (pin "2") (pinfunction "2_2") (pintype "bidirectional"))
      (node (ref "R32") (pin "P$2") (pinfunction "2_P$2") (pintype "passive"))
      (node (ref "SV2") (pin "6") (pinfunction "6_6") (pintype "passive"))
      (node (ref "T13N") (pin "1") (pinfunction "1_1") (pintype "passive"))
    )
    (net (code "26") (name "/GPIO_014_A7") (class "Default")
      (node (ref "SV1") (pin "19") (pinfunction "19_19") (pintype "passive"))
    )
    (net (code "27") (name "/GPIO_14_R13") (class "Default")
      (node (ref "J17") (pin "2") (pinfunction "2_2") (pintype "bidirectional"))
      (node (ref "R13P") (pin "1") (pinfunction "1_1") (pintype "passive"))
      (node (ref "R161") (pin "P$2") (pinfunction "2_P$2") (pintype "passive"))
      (node (ref "SV2") (pin "7") (pinfunction "7_7") (pintype "passive"))
    )
    (net (code "28") (name "/GPIO_015_C6") (class "Default")
      (node (ref "SV1") (pin "20") (pinfunction "20_20") (pintype "passive"))
    )
    (net (code "29") (name "/GPIO_15_T12") (class "Default")
      (node (ref "R18") (pin "2") (pinfunction "2_2") (pintype "passive"))
      (node (ref "S2") (pin "2") (pinfunction "2_2") (pintype "passive"))
      (node (ref "SV2") (pin "8") (pinfunction "8_8") (pintype "passive"))
      (node (ref "U1") (pin "6") (pinfunction "FILTB_6") (pintype "input"))
    )
    (net (code "30") (name "/GPIO_016_C8") (class "Default")
      (node (ref "SV1") (pin "21") (pinfunction "21_21") (pintype "passive"))
    )
    (net (code "31") (name "/GPIO_16_R12") (class "Default")
      (node (ref "SV2") (pin "9") (pinfunction "9_9") (pintype "passive"))
    )
    (net (code "32") (name "/GPIO_017_E6") (class "Default")
      (node (ref "SV1") (pin "22") (pinfunction "22_22") (pintype "passive"))
    )
    (net (code "33") (name "/GPIO_17_T11") (class "Default")
      (node (ref "SV2") (pin "10") (pinfunction "10_10") (pintype "passive"))
    )
    (net (code "34") (name "/GPIO_018_E7") (class "Default")
      (node (ref "SV1") (pin "23") (pinfunction "23_23") (pintype "passive"))
      (node (ref "U4") (pin "6") (pinfunction "1A3_6") (pintype "input"))
      (node (ref "U4") (pin "8") (pinfunction "1A4_8") (pintype "input"))
    )
    (net (code "35") (name "/GPIO_18_T10") (class "Default")
      (node (ref "SV2") (pin "13") (pinfunction "13_13") (pintype "passive"))
    )
    (net (code "36") (name "/GPIO_019_D8") (class "Default")
      (node (ref "SV1") (pin "24") (pinfunction "24_24") (pintype "passive"))
    )
    (net (code "37") (name "/GPIO_19_R11") (class "Default")
      (node (ref "SV2") (pin "14") (pinfunction "14_14") (pintype "passive"))
    )
    (net (code "38") (name "/GPIO_020_E8") (class "Default")
      (node (ref "SV1") (pin "25") (pinfunction "25_25") (pintype "passive"))
    )
    (net (code "39") (name "/GPIO_021_F8") (class "Default")
      (node (ref "SV1") (pin "26") (pinfunction "26_26") (pintype "passive"))
    )
    (net (code "40") (name "/GPIO_022_F9") (class "Default")
      (node (ref "SV1") (pin "27") (pinfunction "27_27") (pintype "passive"))
      (node (ref "U4") (pin "11") (pinfunction "2A1_11") (pintype "input"))
      (node (ref "U4") (pin "13") (pinfunction "2A2_13") (pintype "input"))
    )
    (net (code "41") (name "/GPIO_23_C16") (class "Default")
      (node (ref "U4") (pin "2") (pinfunction "1A1_2") (pintype "input"))
      (node (ref "U4") (pin "4") (pinfunction "1A2_4") (pintype "input"))
    )
    (net (code "42") (name "/GPIO_023_E9") (class "Default")
      (node (ref "SV1") (pin "28") (pinfunction "28_28") (pintype "passive"))
    )
    (net (code "43") (name "/GPIO_024_C9") (class "Default")
      (node (ref "SV1") (pin "31") (pinfunction "31_31") (pintype "passive"))
    )
    (net (code "44") (name "/GPIO_025_D9") (class "Default")
      (node (ref "SV1") (pin "32") (pinfunction "32_32") (pintype "passive"))
    )
    (net (code "45") (name "/GPIO_026_E11") (class "Default")
      (node (ref "SV1") (pin "33") (pinfunction "33_33") (pintype "passive"))
      (node (ref "U3") (pin "2") (pinfunction "1A1_2") (pintype "input"))
      (node (ref "U3") (pin "4") (pinfunction "1A2_4") (pintype "input"))
    )
    (net (code "46") (name "/GPIO_027_E10") (class "Default")
      (node (ref "SV1") (pin "34") (pinfunction "34_34") (pintype "passive"))
    )
    (net (code "47") (name "/GPIO_028_C11") (class "Default")
      (node (ref "SV1") (pin "35") (pinfunction "35_35") (pintype "passive"))
      (node (ref "U3") (pin "11") (pinfunction "2A1_11") (pintype "input"))
      (node (ref "U3") (pin "13") (pinfunction "2A2_13") (pintype "input"))
    )
    (net (code "48") (name "/GPIO_029_B11") (class "Default")
      (node (ref "SV1") (pin "36") (pinfunction "36_36") (pintype "passive"))
    )
    (net (code "49") (name "/GPIO_030_A12") (class "Default")
      (node (ref "SV1") (pin "37") (pinfunction "37_37") (pintype "passive"))
    )
    (net (code "50") (name "/GPIO_031_D11") (class "Default")
      (node (ref "SV1") (pin "38") (pinfunction "38_38") (pintype "passive"))
    )
    (net (code "51") (name "/GPIO_032_D12") (class "Default")
      (node (ref "SV1") (pin "39") (pinfunction "39_39") (pintype "passive"))
    )
    (net (code "52") (name "/GPIO_033_B12") (class "Default")
      (node (ref "SV1") (pin "40") (pinfunction "40_40") (pintype "passive"))
    )
    (net (code "53") (name "/GPIO_110_P11") (class "Default")
      (node (ref "SV2") (pin "15") (pinfunction "15_15") (pintype "passive"))
      (node (ref "U3") (pin "6") (pinfunction "1A3_6") (pintype "input"))
      (node (ref "U3") (pin "8") (pinfunction "1A4_8") (pintype "input"))
    )
    (net (code "54") (name "/GPIO_111_R10") (class "Default")
      (node (ref "SV2") (pin "16") (pinfunction "16_16") (pintype "passive"))
    )
    (net (code "55") (name "/GPIO_112_N12") (class "Default")
      (node (ref "SV2") (pin "17") (pinfunction "17_17") (pintype "passive"))
    )
    (net (code "56") (name "/GPIO_113_P9") (class "Default")
      (node (ref "SV2") (pin "18") (pinfunction "18_18") (pintype "passive"))
      (node (ref "U5") (pin "15") (pinfunction "2A3_15") (pintype "input"))
      (node (ref "U5") (pin "17") (pinfunction "2A4_17") (pintype "input"))
    )
    (net (code "57") (name "/GPIO_114_N9") (class "Default")
      (node (ref "LED1") (pin "A") (pinfunction "A_A") (pintype "passive"))
      (node (ref "R17") (pin "P$2") (pinfunction "2_P$2") (pintype "passive"))
      (node (ref "SV2") (pin "19") (pinfunction "19_19") (pintype "passive"))
      (node (ref "U3") (pin "1") (pinfunction "~{1OE}_1") (pintype "input"))
      (node (ref "U3") (pin "19") (pinfunction "~{2OE}_19") (pintype "input"))
      (node (ref "U4") (pin "1") (pinfunction "~{1OE}_1") (pintype "input"))
      (node (ref "U4") (pin "19") (pinfunction "~{2OE}_19") (pintype "input"))
      (node (ref "U5") (pin "1") (pinfunction "~{1OE}_1") (pintype "input"))
      (node (ref "U5") (pin "19") (pinfunction "~{2OE}_19") (pintype "input"))
    )
    (net (code "58") (name "/GPIO_115_N11") (class "Default")
      (node (ref "SV2") (pin "20") (pinfunction "20_20") (pintype "passive"))
      (node (ref "U5") (pin "11") (pinfunction "2A1_11") (pintype "input"))
      (node (ref "U5") (pin "13") (pinfunction "2A2_13") (pintype "input"))
    )
    (net (code "59") (name "/GPIO_116_L16") (class "Default")
      (node (ref "J32") (pin "2") (pinfunction "2_2") (pintype "bidirectional"))
      (node (ref "L16_R11N") (pin "1") (pinfunction "1_1") (pintype "passive"))
      (node (ref "R15") (pin "1") (pinfunction "1_1") (pintype "passive"))
      (node (ref "R16") (pin "2") (pinfunction "2_2") (pintype "passive"))
      (node (ref "SV2") (pin "21") (pinfunction "21_21") (pintype "passive"))
    )
    (net (code "60") (name "/GPIO_117_K16") (class "Default")
      (node (ref "J23") (pin "2") (pinfunction "2_2") (pintype "bidirectional"))
      (node (ref "K16N") (pin "1") (pinfunction "1_1") (pintype "passive"))
      (node (ref "R22") (pin "P$2") (pinfunction "2_P$2") (pintype "passive"))
      (node (ref "SV2") (pin "22") (pinfunction "22_22") (pintype "passive"))
    )
    (net (code "61") (name "/GPIO_118_R16") (class "Default")
      (node (ref "J34") (pin "2") (pinfunction "2_2") (pintype "bidirectional"))
      (node (ref "R16_R15P") (pin "1") (pinfunction "1_1") (pintype "passive"))
      (node (ref "R3") (pin "1") (pinfunction "1_1") (pintype "passive"))
      (node (ref "R4") (pin "2") (pinfunction "2_2") (pintype "passive"))
      (node (ref "SV2") (pin "23") (pinfunction "23_23") (pintype "passive"))
    )
    (net (code "62") (name "/GPIO_119_L15") (class "Default")
      (node (ref "J43") (pin "2") (pinfunction "2_2") (pintype "bidirectional"))
      (node (ref "L15_R11P") (pin "1") (pinfunction "1_1") (pintype "passive"))
      (node (ref "R11") (pin "1") (pinfunction "1_1") (pintype "passive"))
      (node (ref "R14") (pin "2") (pinfunction "2_2") (pintype "passive"))
      (node (ref "SV2") (pin "24") (pinfunction "24_24") (pintype "passive"))
    )
    (net (code "63") (name "/GPIO_120_P15") (class "Default")
      (node (ref "SV2") (pin "25") (pinfunction "25_25") (pintype "passive"))
      (node (ref "U4") (pin "15") (pinfunction "2A3_15") (pintype "input"))
      (node (ref "U4") (pin "17") (pinfunction "2A4_17") (pintype "input"))
    )
    (net (code "64") (name "/GPIO_121_P16") (class "Default")
      (node (ref "J42") (pin "2") (pinfunction "2_2") (pintype "bidirectional"))
      (node (ref "P16_R15N") (pin "1") (pinfunction "1_1") (pintype "passive"))
      (node (ref "R1") (pin "1") (pinfunction "1_1") (pintype "passive"))
      (node (ref "R2") (pin "2") (pinfunction "2_2") (pintype "passive"))
      (node (ref "SV2") (pin "26") (pinfunction "26_26") (pintype "passive"))
    )
    (net (code "65") (name "/GPIO_122_R14") (class "Default")
      (node (ref "SV2") (pin "27") (pinfunction "27_27") (pintype "passive"))
    )
    (net (code "66") (name "/GPIO_123_N16") (class "Default")
      (node (ref "SV2") (pin "28") (pinfunction "28_28") (pintype "passive"))
    )
    (net (code "67") (name "/GPIO_124_N15") (class "Default")
      (node (ref "SV2") (pin "31") (pinfunction "31_31") (pintype "passive"))
    )
    (net (code "68") (name "/GPIO_125_P14") (class "Default")
      (node (ref "SV2") (pin "32") (pinfunction "32_32") (pintype "passive"))
    )
    (net (code "69") (name "/GPIO_126_L14") (class "Default")
      (node (ref "J7") (pin "2") (pinfunction "P$2_2") (pintype "bidirectional"))
      (node (ref "SV2") (pin "33") (pinfunction "33_33") (pintype "passive"))
    )
    (net (code "70") (name "/GPIO_127_N14") (class "Default")
      (node (ref "SV2") (pin "34") (pinfunction "34_34") (pintype "passive"))
    )
    (net (code "71") (name "/GPIO_128_M10") (class "Default")
      (node (ref "J12") (pin "2") (pinfunction "P$2_2") (pintype "bidirectional"))
      (node (ref "SV2") (pin "35") (pinfunction "35_35") (pintype "passive"))
      (node (ref "U2") (pin "2") (pinfunction "RXD_2") (pintype "input"))
    )
    (net (code "72") (name "/GPIO_129_L13") (class "Default")
      (node (ref "J7") (pin "1") (pinfunction "P$1_1") (pintype "bidirectional"))
      (node (ref "SV2") (pin "36") (pinfunction "36_36") (pintype "passive"))
    )
    (net (code "73") (name "/GPIO_130_J16") (class "Default")
      (node (ref "J12") (pin "1") (pinfunction "P$1_1") (pintype "bidirectional"))
      (node (ref "SV2") (pin "37") (pinfunction "37_37") (pintype "passive"))
      (node (ref "U2") (pin "15") (pinfunction "TXD_15") (pintype "output"))
    )
    (net (code "74") (name "/GPIO_131_K15") (class "Default")
      (node (ref "J24") (pin "2") (pinfunction "2_2") (pintype "bidirectional"))
      (node (ref "K15P") (pin "1") (pinfunction "1_1") (pintype "passive"))
      (node (ref "R23") (pin "P$2") (pinfunction "2_P$2") (pintype "passive"))
      (node (ref "SV2") (pin "38") (pinfunction "38_38") (pintype "passive"))
    )
    (net (code "75") (name "/GPIO_132_J13") (class "Default")
      (node (ref "SV2") (pin "39") (pinfunction "39_39") (pintype "passive"))
      (node (ref "U3") (pin "15") (pinfunction "2A3_15") (pintype "input"))
      (node (ref "U3") (pin "17") (pinfunction "2A4_17") (pintype "input"))
    )
    (net (code "76") (name "/GPIO_133_J14") (class "Default")
      (node (ref "SV2") (pin "40") (pinfunction "40_40") (pintype "passive"))
    )
    (net (code "77") (name "Net-(C1-Pad1)") (class "Default")
      (node (ref "C1") (pin "1") (pinfunction "1_1") (pintype "passive"))
      (node (ref "CLK-IN+") (pin "1") (pinfunction "1_1") (pintype "passive"))
      (node (ref "R5") (pin "2") (pinfunction "2_2") (pintype "passive"))
    )
    (net (code "78") (name "Net-(C3-Pad1)") (class "Default")
      (node (ref "C3") (pin "1") (pinfunction "1_1") (pintype "passive"))
      (node (ref "CLK-IN-") (pin "1") (pinfunction "1_1") (pintype "passive"))
      (node (ref "R6") (pin "2") (pinfunction "2_2") (pintype "passive"))
    )
    (net (code "79") (name "Net-(J1-D+)") (class "Default")
      (node (ref "C12") (pin "1") (pinfunction "1_1") (pintype "passive"))
      (node (ref "J1") (pin "3") (pinfunction "D+_3") (pintype "bidirectional"))
      (node (ref "R10") (pin "1") (pinfunction "1_1") (pintype "passive"))
    )
    (net (code "80") (name "Net-(J1-D-)") (class "Default")
      (node (ref "C10") (pin "2") (pinfunction "2_2") (pintype "passive"))
      (node (ref "J1") (pin "2") (pinfunction "D-_2") (pintype "bidirectional"))
      (node (ref "R12") (pin "1") (pinfunction "1_1") (pintype "passive"))
    )
    (net (code "81") (name "Net-(J1-VCC)") (class "Default")
      (node (ref "C5") (pin "2") (pinfunction "2_2") (pintype "passive"))
      (node (ref "FB1") (pin "1") (pinfunction "1_1") (pintype "passive"))
      (node (ref "J1") (pin "1") (pinfunction "VCC_1") (pintype "power_in"))
    )
    (net (code "82") (name "Net-(LED1-PadC)") (class "Default")
      (node (ref "LED1") (pin "C") (pinfunction "C_C") (pintype "passive"))
      (node (ref "R8") (pin "1") (pinfunction "1_1") (pintype "passive"))
    )
    (net (code "83") (name "Net-(U1-IN+)") (class "Default")
      (node (ref "C1") (pin "2") (pinfunction "2_2") (pintype "passive"))
      (node (ref "U1") (pin "3") (pinfunction "IN+_3") (pintype "input"))
    )
    (net (code "84") (name "Net-(U1-IN-)") (class "Default")
      (node (ref "C3") (pin "2") (pinfunction "2_2") (pintype "passive"))
      (node (ref "U1") (pin "4") (pinfunction "IN-_4") (pintype "input"))
    )
    (net (code "85") (name "Net-(U2-3V3OUT)") (class "Default")
      (node (ref "C9") (pin "1") (pinfunction "1_1") (pintype "passive"))
      (node (ref "U2") (pin "1") (pinfunction "VCCIO_1") (pintype "power_in"))
      (node (ref "U2") (pin "8") (pinfunction "3V3OUT_8") (pintype "output"))
      (node (ref "U2") (pin "9") (pinfunction "~{RESET}_9") (pintype "input"))
    )
    (net (code "86") (name "Net-(U2-USBDM)") (class "Default")
      (node (ref "R12") (pin "2") (pinfunction "2_2") (pintype "passive"))
      (node (ref "U2") (pin "7") (pinfunction "USBDM_7") (pintype "input"))
    )
    (net (code "87") (name "Net-(U2-USBDP)") (class "Default")
      (node (ref "R10") (pin "2") (pinfunction "2_2") (pintype "passive"))
      (node (ref "U2") (pin "6") (pinfunction "USBDP_6") (pintype "input"))
    )
    (net (code "88") (name "Net-(U3-1Y1)") (class "Default")
      (node (ref "E11") (pin "1") (pinfunction "1_1") (pintype "passive"))
      (node (ref "OJ76") (pin "1") (pinfunction "1_1") (pintype "bidirectional"))
      (node (ref "U3") (pin "16") (pinfunction "1Y2_16") (pintype "output"))
      (node (ref "U3") (pin "18") (pinfunction "1Y1_18") (pintype "output"))
    )
    (net (code "89") (name "Net-(U3-1Y3)") (class "Default")
      (node (ref "OJ75") (pin "1") (pinfunction "1_1") (pintype "bidirectional"))
      (node (ref "P11") (pin "1") (pinfunction "1_1") (pintype "passive"))
      (node (ref "U3") (pin "12") (pinfunction "1Y4_12") (pintype "output"))
      (node (ref "U3") (pin "14") (pinfunction "1Y3_14") (pintype "output"))
    )
    (net (code "90") (name "Net-(U3-2Y1)") (class "Default")
      (node (ref "C11") (pin "1") (pinfunction "1_1") (pintype "passive"))
      (node (ref "OJ74") (pin "1") (pinfunction "1_1") (pintype "bidirectional"))
      (node (ref "U3") (pin "7") (pinfunction "2Y2_7") (pintype "output"))
      (node (ref "U3") (pin "9") (pinfunction "2Y1_9") (pintype "output"))
    )
    (net (code "91") (name "Net-(U3-2Y3)") (class "Default")
      (node (ref "J13") (pin "1") (pinfunction "1_1") (pintype "passive"))
      (node (ref "OJ73") (pin "1") (pinfunction "1_1") (pintype "bidirectional"))
      (node (ref "U3") (pin "3") (pinfunction "2Y4_3") (pintype "output"))
      (node (ref "U3") (pin "5") (pinfunction "2Y3_5") (pintype "output"))
    )
    (net (code "92") (name "Net-(U4-1Y1)") (class "Default")
      (node (ref "C16") (pin "1") (pinfunction "1_1") (pintype "passive"))
      (node (ref "OJ60") (pin "1") (pinfunction "1_1") (pintype "bidirectional"))
      (node (ref "U4") (pin "16") (pinfunction "1Y2_16") (pintype "output"))
      (node (ref "U4") (pin "18") (pinfunction "1Y1_18") (pintype "output"))
    )
    (net (code "93") (name "Net-(U4-1Y3)") (class "Default")
      (node (ref "E7") (pin "1") (pinfunction "1_1") (pintype "passive"))
      (node (ref "OJ59") (pin "1") (pinfunction "1_1") (pintype "bidirectional"))
      (node (ref "U4") (pin "12") (pinfunction "1Y4_12") (pintype "output"))
      (node (ref "U4") (pin "14") (pinfunction "1Y3_14") (pintype "output"))
    )
    (net (code "94") (name "Net-(U4-2Y1)") (class "Default")
      (node (ref "F9") (pin "1") (pinfunction "1_1") (pintype "passive"))
      (node (ref "OJ58") (pin "1") (pinfunction "1_1") (pintype "bidirectional"))
      (node (ref "U4") (pin "7") (pinfunction "2Y2_7") (pintype "output"))
      (node (ref "U4") (pin "9") (pinfunction "2Y1_9") (pintype "output"))
    )
    (net (code "95") (name "Net-(U4-2Y3)") (class "Default")
      (node (ref "OJ57") (pin "1") (pinfunction "1_1") (pintype "bidirectional"))
      (node (ref "P15") (pin "1") (pinfunction "1_1") (pintype "passive"))
      (node (ref "U4") (pin "3") (pinfunction "2Y4_3") (pintype "output"))
      (node (ref "U4") (pin "5") (pinfunction "2Y3_5") (pintype "output"))
    )
    (net (code "96") (name "Net-(U5-1Y1)") (class "Default")
      (node (ref "B6") (pin "1") (pinfunction "1_1") (pintype "passive"))
      (node (ref "OJ44") (pin "1") (pinfunction "1_1") (pintype "bidirectional"))
      (node (ref "U5") (pin "16") (pinfunction "1Y2_16") (pintype "output"))
      (node (ref "U5") (pin "18") (pinfunction "1Y1_18") (pintype "output"))
    )
    (net (code "97") (name "Net-(U5-1Y3)") (class "Default")
      (node (ref "A6") (pin "1") (pinfunction "1_1") (pintype "passive"))
      (node (ref "OJ43") (pin "1") (pinfunction "1_1") (pintype "bidirectional"))
      (node (ref "U5") (pin "12") (pinfunction "1Y4_12") (pintype "output"))
      (node (ref "U5") (pin "14") (pinfunction "1Y3_14") (pintype "output"))
    )
    (net (code "98") (name "Net-(U5-2Y1)") (class "Default")
      (node (ref "N11") (pin "1") (pinfunction "1_1") (pintype "passive"))
      (node (ref "OJ42") (pin "1") (pinfunction "1_1") (pintype "bidirectional"))
      (node (ref "U5") (pin "7") (pinfunction "2Y2_7") (pintype "output"))
      (node (ref "U5") (pin "9") (pinfunction "2Y1_9") (pintype "output"))
    )
    (net (code "99") (name "Net-(U5-2Y3)") (class "Default")
      (node (ref "OJ41") (pin "1") (pinfunction "1_1") (pintype "bidirectional"))
      (node (ref "P9") (pin "1") (pinfunction "1_1") (pintype "passive"))
      (node (ref "U5") (pin "3") (pinfunction "2Y4_3") (pintype "output"))
      (node (ref "U5") (pin "5") (pinfunction "2Y3_5") (pintype "output"))
    )
    (net (code "100") (name "unconnected-(J1-ID-Pad4)") (class "Default")
      (node (ref "J1") (pin "4") (pinfunction "ID_4") (pintype "bidirectional"))
    )
    (net (code "101") (name "unconnected-(U2-CBUS0-Pad12)") (class "Default")
      (node (ref "U2") (pin "12") (pinfunction "CBUS0_12") (pintype "bidirectional"))
    )
    (net (code "102") (name "unconnected-(U2-CBUS1-Pad11)") (class "Default")
      (node (ref "U2") (pin "11") (pinfunction "CBUS1_11") (pintype "bidirectional"))
    )
    (net (code "103") (name "unconnected-(U2-CBUS2-Pad5)") (class "Default")
      (node (ref "U2") (pin "5") (pinfunction "CBUS2_5") (pintype "bidirectional"))
    )
    (net (code "104") (name "unconnected-(U2-CBUS3-Pad14)") (class "Default")
      (node (ref "U2") (pin "14") (pinfunction "CBUS3_14") (pintype "bidirectional"))
    )
    (net (code "105") (name "unconnected-(U2-~{CTS}-Pad4)") (class "Default")
      (node (ref "U2") (pin "4") (pinfunction "~{CTS}_4") (pintype "input"))
    )
    (net (code "106") (name "unconnected-(U2-~{RTS}-Pad16)") (class "Default")
      (node (ref "U2") (pin "16") (pinfunction "~{RTS}_16") (pintype "output"))
    )
  )
)
